# in_channel.net
KiCad netlist of a schematic drawn in Altium Designer
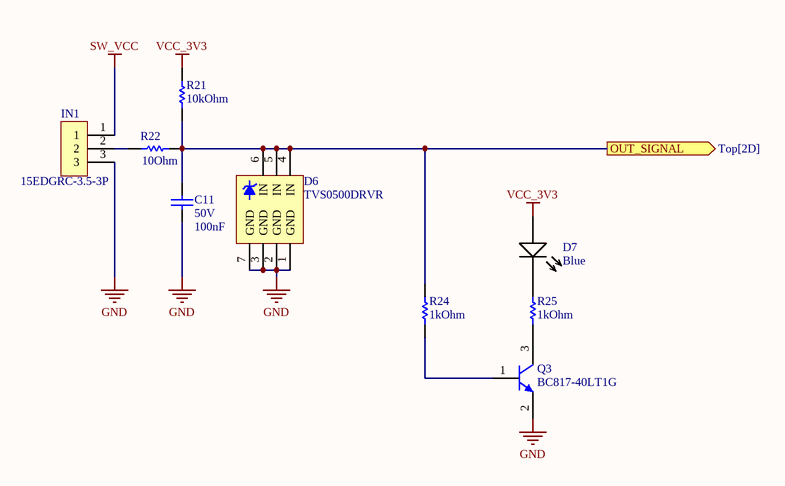
[diagram p0: in_channel.SchDoc]

(export (version "E")
  (design (tool "Eeschema 10.0.6"))
  (components
    (comp (ref "C11")
      (value "~")
      (footprint "CAP_0603_High_density")
      (description "Generic Ceramic Capacitor SMD")
      (fields
        (field (name "TOLERANCE") "10%")
        (field (name "VOLTAGE") "50V")
        (field (name "CAPACITANCE") "100nF")
      )
      (libsource (lib "altium_conclusive_library") (part "Capacitor SMD"))
    )
    (comp (ref "D6")
      (value "TVS0500DRVR")
      (footprint "FP-DRV0006A-IPC_C")
      (description "ESD Suppressors / TVS Diodes 5V flat-clamp surge protection device 6-WSON -40 to 125")
      (libsource (lib "MY_LIB") (part "TVS0500DRVR"))
    )
    (comp (ref "D7")
      (value "C84266")
      (footprint "LED_0603")
      (description "Generic LED diode SMD Blue")
      (fields (field (name "COLOUR") "Blue"))
      (libsource (lib "MY_LIB") (part "LED diode"))
    )
    (comp (ref "IN1")
      (value "15EDGRC-3.5-3P")
      (footprint "15EDGRC-3.5 - 3 PIN")
      (description "15EDGRC-3.5 - 3 pin")
      (libsource (lib "MY_LIB") (part "15EDGRC-3.5-3P"))
    )
    (comp (ref "Q3")
      (value "BC817-40LT1G")
      (footprint "SOT-23A")
      (description "General Purpose Transistor, NPN Silicon, 3-Pin SOT-23, Pb-Free, Tape and Reel")
      (fields (field (name "MANUFACTURER") "On Semiconductor"))
      (libsource (lib "MY_LIB") (part "BC817-40LT1G"))
    )
    (comp (ref "R21")
      (value "0603 10kOhm 1%")
      (footprint "RES_0603")
      (description "Generic Resistor SMD")
      (fields (field (name "RESISTANCE") "10kOhm"))
      (libsource (lib "MY_LIB") (part "Resistor SMD_1"))
    )
    (comp (ref "R22")
      (value "0603 10Ohm 1%")
      (footprint "RES_0603")
      (description "Generic Resistor SMD")
      (fields (field (name "RESISTANCE") "10Ohm"))
      (libsource (lib "MY_LIB") (part "Resistor SMD_1"))
    )
    (comp (ref "R24")
      (value "0603 1kOhm 1%")
      (footprint "RES_0603")
      (description "Generic Resistor SMD")
      (fields (field (name "RESISTANCE") "1kOhm"))
      (libsource (lib "MY_LIB") (part "Resistor SMD_1"))
    )
    (comp (ref "R25")
      (value "0603 1kOhm 1%")
      (footprint "RES_0603")
      (description "Generic Resistor SMD")
      (fields (field (name "RESISTANCE") "1kOhm"))
      (libsource (lib "MY_LIB") (part "Resistor SMD_1"))
    )
  )
  (nets
    (net (code "1") (name "/OUT_SIGNAL") (class "Default")
      (node (ref "C11") (pin "1") (pinfunction "1_1") (pintype "passive"))
      (node (ref "D6") (pin "4") (pinfunction "IN_4") (pintype "passive"))
      (node (ref "D6") (pin "5") (pinfunction "IN_5") (pintype "passive"))
      (node (ref "D6") (pin "6") (pinfunction "IN_6") (pintype "passive"))
      (node (ref "R21") (pin "2") (pinfunction "2_2") (pintype "passive"))
      (node (ref "R22") (pin "2") (pinfunction "2_2") (pintype "passive"))
      (node (ref "R24") (pin "2") (pinfunction "2_2") (pintype "passive"))
    )
    (net (code "2") (name "GND") (class "Default")
      (node (ref "C11") (pin "2") (pinfunction "2_2") (pintype "passive"))
      (node (ref "D6") (pin "1") (pinfunction "GND_1") (pintype "power_in"))
      (node (ref "D6") (pin "2") (pinfunction "GND_2") (pintype "power_in"))
      (node (ref "D6") (pin "3") (pinfunction "GND_3") (pintype "power_in"))
      (node (ref "D6") (pin "7") (pinfunction "GND_7") (pintype "power_in"))
      (node (ref "IN1") (pin "3") (pinfunction "3_3") (pintype "passive"))
      (node (ref "Q3") (pin "2") (pinfunction "E_2") (pintype "passive"))
    )
    (net (code "3") (name "Net-(D7-PadC)") (class "Default")
      (node (ref "D7") (pin "C") (pinfunction "C_C") (pintype "passive"))
      (node (ref "R25") (pin "2") (pinfunction "2_2") (pintype "passive"))
    )
    (net (code "4") (name "Net-(IN1-Pad2)") (class "Default")
      (node (ref "IN1") (pin "2") (pinfunction "2_2") (pintype "passive"))
      (node (ref "R22") (pin "1") (pinfunction "1_1") (pintype "passive"))
    )
    (net (code "5") (name "Net-(Q3-C)") (class "Default")
      (node (ref "Q3") (pin "3") (pinfunction "C_3") (pintype "passive"))
      (node (ref "R25") (pin "1") (pinfunction "1_1") (pintype "passive"))
    )
    (net (code "6") (name "Net-(Q3-Pad1)") (class "Default")
      (node (ref "Q3") (pin "1") (pinfunction "1_1") (pintype "passive"))
      (node (ref "R24") (pin "1") (pinfunction "1_1") (pintype "passive"))
    )
    (net (code "7") (name "SW_VCC") (class "Default")
      (node (ref "IN1") (pin "1") (pinfunction "1_1") (pintype "passive"))
    )
    (net (code "8") (name "VCC_3V3") (class "Default")
      (node (ref "D7") (pin "A") (pinfunction "A_A") (pintype "passive"))
      (node (ref "R21") (pin "1") (pinfunction "1_1") (pintype "passive"))
    )
  )
)
